# vds_topboard_revC.net
KiCad netlist of a schematic drawn in EAGLE
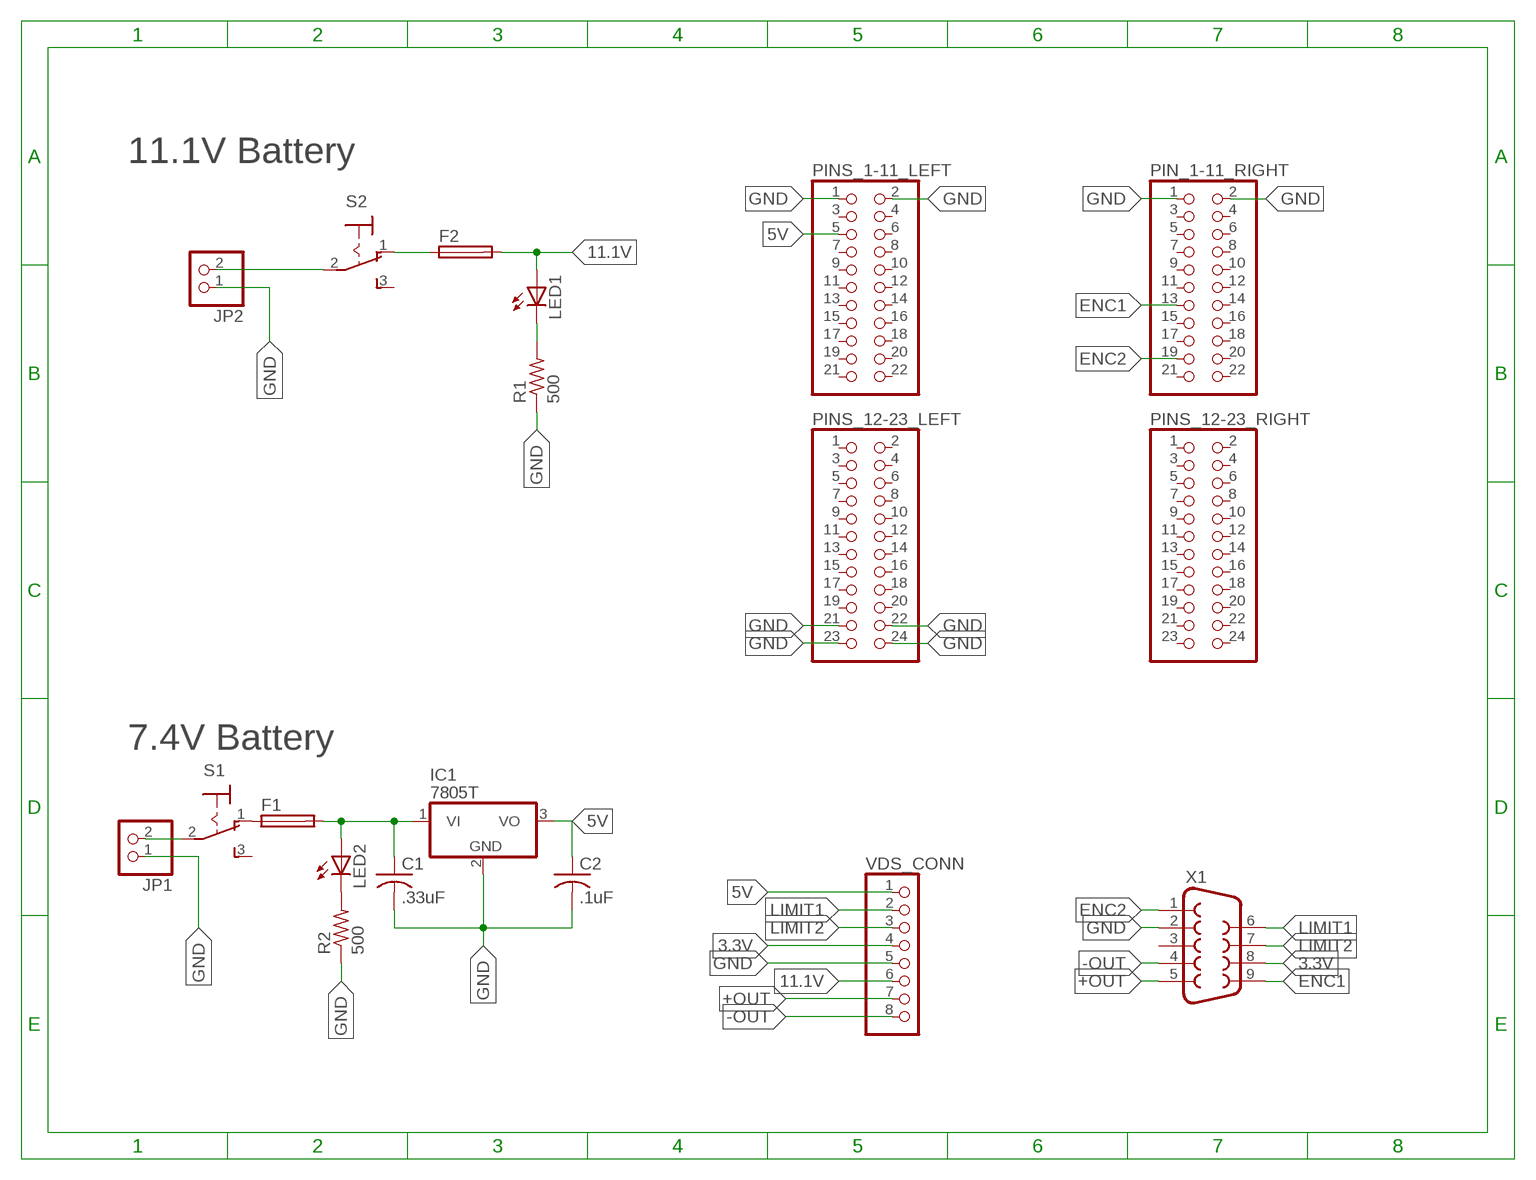
[diagram p0: schematic, sheet 1]

(export (version "E")
  (design (tool "Eeschema 10.0.6"))
  (components
    (comp (ref "C1")
      (value ".33uF")
      (footprint "eagle-import:C025-030X050")
      (libsource (lib "eagle-import") (part "C-US025-030X050"))
    )
    (comp (ref "C2")
      (value ".1uF")
      (footprint "eagle-import:C025-030X050")
      (libsource (lib "eagle-import") (part "C-US025-030X050"))
    )
    (comp (ref "F1")
      (value "SH22,5")
      (footprint "eagle-import:SH22,5")
      (fields (field (name "MF") "SCHURTER") (field (name "MPN") "0031.8201"))
      (libsource (lib "eagle-import") (part "SH22,5"))
    )
    (comp (ref "F2")
      (value "SH22,5")
      (footprint "eagle-import:SH22,5")
      (fields (field (name "MF") "SCHURTER") (field (name "MPN") "0031.8201"))
      (libsource (lib "eagle-import") (part "SH22,5"))
    )
    (comp (ref "IC1")
      (value "7805T")
      (footprint "eagle-import:TO220H")
      (libsource (lib "eagle-import") (part "78T05"))
    )
    (comp (ref "JP1")
      (value "PINHD-1X2")
      (footprint "eagle-import:1X02")
      (libsource (lib "eagle-import") (part "PINHD-1X2"))
    )
    (comp (ref "JP2")
      (value "PINHD-1X2")
      (footprint "eagle-import:1X02")
      (libsource (lib "eagle-import") (part "PINHD-1X2"))
    )
    (comp (ref "LED1")
      (value "LED5MM")
      (footprint "eagle-import:LED5MM")
      (libsource (lib "eagle-import") (part "LED5MM"))
    )
    (comp (ref "LED2")
      (value "LED5MM")
      (footprint "eagle-import:LED5MM")
      (libsource (lib "eagle-import") (part "LED5MM"))
    )
    (comp (ref "PINS_1-11_LEFT")
      (value "PINHD-2X11")
      (footprint "eagle-import:2X11")
      (libsource (lib "eagle-import") (part "PINHD-2X11"))
    )
    (comp (ref "PINS_12-23_LEFT")
      (value "PINHD-2X12")
      (footprint "eagle-import:2X12")
      (libsource (lib "eagle-import") (part "PINHD-2X12"))
    )
    (comp (ref "PINS_12-23_RIGHT")
      (value "PINHD-2X12")
      (footprint "eagle-import:2X12")
      (libsource (lib "eagle-import") (part "PINHD-2X12"))
    )
    (comp (ref "PIN_1-11_RIGHT")
      (value "PINHD-2X11")
      (footprint "eagle-import:2X11")
      (libsource (lib "eagle-import") (part "PINHD-2X11"))
    )
    (comp (ref "R1")
      (value "500")
      (footprint "eagle-import:0204_5")
      (libsource (lib "eagle-import") (part "R-US_0204/5"))
    )
    (comp (ref "R2")
      (value "500")
      (footprint "eagle-import:0204_5")
      (libsource (lib "eagle-import") (part "R-US_0204/5"))
    )
    (comp (ref "S1")
      (value "320-916")
      (footprint "eagle-import:320-916")
      (libsource (lib "eagle-import") (part "320-916"))
    )
    (comp (ref "S2")
      (value "320-916")
      (footprint "eagle-import:320-916")
      (libsource (lib "eagle-import") (part "320-916"))
    )
    (comp (ref "VDS_CONN")
      (value "PINHD-1X8")
      (footprint "eagle-import:1X08")
      (libsource (lib "eagle-import") (part "PINHD-1X8"))
    )
    (comp (ref "X1")
      (value "F09VP")
      (footprint "eagle-import:F09VP")
      (libsource (lib "eagle-import") (part "F09VP"))
    )
  )
  (nets
    (net (code "1") (name "+OUT") (class "Default")
      (node (ref "VDS_CONN") (pin "7") (pinfunction "7_7") (pintype "passive"))
      (node (ref "X1") (pin "5") (pinfunction "5_5") (pintype "passive"))
    )
    (net (code "2") (name "-OUT") (class "Default")
      (node (ref "VDS_CONN") (pin "8") (pinfunction "8_8") (pintype "passive"))
      (node (ref "X1") (pin "4") (pinfunction "4_4") (pintype "passive"))
    )
    (net (code "3") (name "3.3V") (class "Default")
      (node (ref "VDS_CONN") (pin "4") (pinfunction "4_4") (pintype "passive"))
      (node (ref "X1") (pin "8") (pinfunction "8_8") (pintype "passive"))
    )
    (net (code "4") (name "5V") (class "Default")
      (node (ref "C2") (pin "1") (pinfunction "1_1") (pintype "passive"))
      (node (ref "IC1") (pin "3") (pinfunction "VO_3") (pintype "passive"))
      (node (ref "PINS_1-11_LEFT") (pin "5") (pinfunction "5_5") (pintype "passive"))
      (node (ref "VDS_CONN") (pin "1") (pinfunction "1_1") (pintype "passive"))
    )
    (net (code "5") (name "11.1V") (class "Default")
      (node (ref "F2") (pin "2") (pinfunction "2_2") (pintype "passive"))
      (node (ref "LED1") (pin "A") (pinfunction "A_A") (pintype "passive"))
      (node (ref "VDS_CONN") (pin "6") (pinfunction "6_6") (pintype "passive"))
    )
    (net (code "6") (name "ENC1") (class "Default")
      (node (ref "PIN_1-11_RIGHT") (pin "13") (pinfunction "13_13") (pintype "passive"))
      (node (ref "X1") (pin "9") (pinfunction "9_9") (pintype "passive"))
    )
    (net (code "7") (name "ENC2") (class "Default")
      (node (ref "PIN_1-11_RIGHT") (pin "19") (pinfunction "19_19") (pintype "passive"))
      (node (ref "X1") (pin "1") (pinfunction "1_1") (pintype "passive"))
    )
    (net (code "8") (name "GND") (class "Default")
      (node (ref "C1") (pin "2") (pinfunction "2_2") (pintype "passive"))
      (node (ref "C2") (pin "2") (pinfunction "2_2") (pintype "passive"))
      (node (ref "IC1") (pin "2") (pinfunction "GND_2") (pintype "passive"))
      (node (ref "JP1") (pin "1") (pinfunction "1_1") (pintype "passive"))
      (node (ref "JP2") (pin "1") (pinfunction "1_1") (pintype "passive"))
      (node (ref "PINS_1-11_LEFT") (pin "1") (pinfunction "1_1") (pintype "passive"))
      (node (ref "PINS_1-11_LEFT") (pin "2") (pinfunction "2_2") (pintype "passive"))
      (node (ref "PINS_12-23_LEFT") (pin "21") (pinfunction "21_21") (pintype "passive"))
      (node (ref "PINS_12-23_LEFT") (pin "22") (pinfunction "22_22") (pintype "passive"))
      (node (ref "PINS_12-23_LEFT") (pin "23") (pinfunction "23_23") (pintype "passive"))
      (node (ref "PINS_12-23_LEFT") (pin "24") (pinfunction "24_24") (pintype "passive"))
      (node (ref "PIN_1-11_RIGHT") (pin "1") (pinfunction "1_1") (pintype "passive"))
      (node (ref "PIN_1-11_RIGHT") (pin "2") (pinfunction "2_2") (pintype "passive"))
      (node (ref "R1") (pin "1") (pinfunction "1_1") (pintype "passive"))
      (node (ref "R2") (pin "1") (pinfunction "1_1") (pintype "passive"))
      (node (ref "VDS_CONN") (pin "5") (pinfunction "5_5") (pintype "passive"))
      (node (ref "X1") (pin "2") (pinfunction "2_2") (pintype "passive"))
    )
    (net (code "9") (name "LIMIT1") (class "Default")
      (node (ref "VDS_CONN") (pin "2") (pinfunction "2_2") (pintype "passive"))
      (node (ref "X1") (pin "6") (pinfunction "6_6") (pintype "passive"))
    )
    (net (code "10") (name "LIMIT2") (class "Default")
      (node (ref "VDS_CONN") (pin "3") (pinfunction "3_3") (pintype "passive"))
      (node (ref "X1") (pin "7") (pinfunction "7_7") (pintype "passive"))
    )
    (net (code "11") (name "Net-(IC1-VI)") (class "Default")
      (node (ref "C1") (pin "1") (pinfunction "1_1") (pintype "passive"))
      (node (ref "F1") (pin "2") (pinfunction "2_2") (pintype "passive"))
      (node (ref "IC1") (pin "1") (pinfunction "VI_1") (pintype "input"))
      (node (ref "LED2") (pin "A") (pinfunction "A_A") (pintype "passive"))
    )
    (net (code "12") (name "Net-(LED1-C)") (class "Default")
      (node (ref "LED1") (pin "K") (pinfunction "C_K") (pintype "passive"))
      (node (ref "R1") (pin "2") (pinfunction "2_2") (pintype "passive"))
    )
    (net (code "13") (name "Net-(LED2-C)") (class "Default")
      (node (ref "LED2") (pin "K") (pinfunction "C_K") (pintype "passive"))
      (node (ref "R2") (pin "2") (pinfunction "2_2") (pintype "passive"))
    )
    (net (code "14") (name "Net-(S1-O)") (class "Default")
      (node (ref "F1") (pin "1") (pinfunction "1_1") (pintype "passive"))
      (node (ref "S1") (pin "1") (pinfunction "O_1") (pintype "passive"))
    )
    (net (code "15") (name "Net-(S1-P)") (class "Default")
      (node (ref "JP1") (pin "2") (pinfunction "2_2") (pintype "passive"))
      (node (ref "S1") (pin "2") (pinfunction "P_2") (pintype "passive"))
    )
    (net (code "16") (name "Net-(S2-O)") (class "Default")
      (node (ref "F2") (pin "1") (pinfunction "1_1") (pintype "passive"))
      (node (ref "S2") (pin "1") (pinfunction "O_1") (pintype "passive"))
    )
    (net (code "17") (name "Net-(S2-P)") (class "Default")
      (node (ref "JP2") (pin "2") (pinfunction "2_2") (pintype "passive"))
      (node (ref "S2") (pin "2") (pinfunction "P_2") (pintype "passive"))
    )
    (net (code "18") (name "unconnected-(PINS_1-11_LEFT-Pad3)") (class "Default")
      (node (ref "PINS_1-11_LEFT") (pin "3") (pinfunction "3_3") (pintype "passive"))
    )
    (net (code "19") (name "unconnected-(PINS_1-11_LEFT-Pad4)") (class "Default")
      (node (ref "PINS_1-11_LEFT") (pin "4") (pinfunction "4_4") (pintype "passive"))
    )
    (net (code "20") (name "unconnected-(PINS_1-11_LEFT-Pad6)") (class "Default")
      (node (ref "PINS_1-11_LEFT") (pin "6") (pinfunction "6_6") (pintype "passive"))
    )
    (net (code "21") (name "unconnected-(PINS_1-11_LEFT-Pad7)") (class "Default")
      (node (ref "PINS_1-11_LEFT") (pin "7") (pinfunction "7_7") (pintype "passive"))
    )
    (net (code "22") (name "unconnected-(PINS_1-11_LEFT-Pad8)") (class "Default")
      (node (ref "PINS_1-11_LEFT") (pin "8") (pinfunction "8_8") (pintype "passive"))
    )
    (net (code "23") (name "unconnected-(PINS_1-11_LEFT-Pad9)") (class "Default")
      (node (ref "PINS_1-11_LEFT") (pin "9") (pinfunction "9_9") (pintype "passive"))
    )
    (net (code "24") (name "unconnected-(PINS_1-11_LEFT-Pad10)") (class "Default")
      (node (ref "PINS_1-11_LEFT") (pin "10") (pinfunction "10_10") (pintype "passive"))
    )
    (net (code "25") (name "unconnected-(PINS_1-11_LEFT-Pad11)") (class "Default")
      (node (ref "PINS_1-11_LEFT") (pin "11") (pinfunction "11_11") (pintype "passive"))
    )
    (net (code "26") (name "unconnected-(PINS_1-11_LEFT-Pad12)") (class "Default")
      (node (ref "PINS_1-11_LEFT") (pin "12") (pinfunction "12_12") (pintype "passive"))
    )
    (net (code "27") (name "unconnected-(PINS_1-11_LEFT-Pad13)") (class "Default")
      (node (ref "PINS_1-11_LEFT") (pin "13") (pinfunction "13_13") (pintype "passive"))
    )
    (net (code "28") (name "unconnected-(PINS_1-11_LEFT-Pad14)") (class "Default")
      (node (ref "PINS_1-11_LEFT") (pin "14") (pinfunction "14_14") (pintype "passive"))
    )
    (net (code "29") (name "unconnected-(PINS_1-11_LEFT-Pad15)") (class "Default")
      (node (ref "PINS_1-11_LEFT") (pin "15") (pinfunction "15_15") (pintype "passive"))
    )
    (net (code "30") (name "unconnected-(PINS_1-11_LEFT-Pad16)") (class "Default")
      (node (ref "PINS_1-11_LEFT") (pin "16") (pinfunction "16_16") (pintype "passive"))
    )
    (net (code "31") (name "unconnected-(PINS_1-11_LEFT-Pad17)") (class "Default")
      (node (ref "PINS_1-11_LEFT") (pin "17") (pinfunction "17_17") (pintype "passive"))
    )
    (net (code "32") (name "unconnected-(PINS_1-11_LEFT-Pad18)") (class "Default")
      (node (ref "PINS_1-11_LEFT") (pin "18") (pinfunction "18_18") (pintype "passive"))
    )
    (net (code "33") (name "unconnected-(PINS_1-11_LEFT-Pad19)") (class "Default")
      (node (ref "PINS_1-11_LEFT") (pin "19") (pinfunction "19_19") (pintype "passive"))
    )
    (net (code "34") (name "unconnected-(PINS_1-11_LEFT-Pad20)") (class "Default")
      (node (ref "PINS_1-11_LEFT") (pin "20") (pinfunction "20_20") (pintype "passive"))
    )
    (net (code "35") (name "unconnected-(PINS_1-11_LEFT-Pad21)") (class "Default")
      (node (ref "PINS_1-11_LEFT") (pin "21") (pinfunction "21_21") (pintype "passive"))
    )
    (net (code "36") (name "unconnected-(PINS_1-11_LEFT-Pad22)") (class "Default")
      (node (ref "PINS_1-11_LEFT") (pin "22") (pinfunction "22_22") (pintype "passive"))
    )
    (net (code "37") (name "unconnected-(PINS_12-23_LEFT-Pad1)") (class "Default")
      (node (ref "PINS_12-23_LEFT") (pin "1") (pinfunction "1_1") (pintype "passive"))
    )
    (net (code "38") (name "unconnected-(PINS_12-23_LEFT-Pad2)") (class "Default")
      (node (ref "PINS_12-23_LEFT") (pin "2") (pinfunction "2_2") (pintype "passive"))
    )
    (net (code "39") (name "unconnected-(PINS_12-23_LEFT-Pad3)") (class "Default")
      (node (ref "PINS_12-23_LEFT") (pin "3") (pinfunction "3_3") (pintype "passive"))
    )
    (net (code "40") (name "unconnected-(PINS_12-23_LEFT-Pad4)") (class "Default")
      (node (ref "PINS_12-23_LEFT") (pin "4") (pinfunction "4_4") (pintype "passive"))
    )
    (net (code "41") (name "unconnected-(PINS_12-23_LEFT-Pad5)") (class "Default")
      (node (ref "PINS_12-23_LEFT") (pin "5") (pinfunction "5_5") (pintype "passive"))
    )
    (net (code "42") (name "unconnected-(PINS_12-23_LEFT-Pad6)") (class "Default")
      (node (ref "PINS_12-23_LEFT") (pin "6") (pinfunction "6_6") (pintype "passive"))
    )
    (net (code "43") (name "unconnected-(PINS_12-23_LEFT-Pad7)") (class "Default")
      (node (ref "PINS_12-23_LEFT") (pin "7") (pinfunction "7_7") (pintype "passive"))
    )
    (net (code "44") (name "unconnected-(PINS_12-23_LEFT-Pad8)") (class "Default")
      (node (ref "PINS_12-23_LEFT") (pin "8") (pinfunction "8_8") (pintype "passive"))
    )
    (net (code "45") (name "unconnected-(PINS_12-23_LEFT-Pad9)") (class "Default")
      (node (ref "PINS_12-23_LEFT") (pin "9") (pinfunction "9_9") (pintype "passive"))
    )
    (net (code "46") (name "unconnected-(PINS_12-23_LEFT-Pad10)") (class "Default")
      (node (ref "PINS_12-23_LEFT") (pin "10") (pinfunction "10_10") (pintype "passive"))
    )
    (net (code "47") (name "unconnected-(PINS_12-23_LEFT-Pad11)") (class "Default")
      (node (ref "PINS_12-23_LEFT") (pin "11") (pinfunction "11_11") (pintype "passive"))
    )
    (net (code "48") (name "unconnected-(PINS_12-23_LEFT-Pad12)") (class "Default")
      (node (ref "PINS_12-23_LEFT") (pin "12") (pinfunction "12_12") (pintype "passive"))
    )
    (net (code "49") (name "unconnected-(PINS_12-23_LEFT-Pad13)") (class "Default")
      (node (ref "PINS_12-23_LEFT") (pin "13") (pinfunction "13_13") (pintype "passive"))
    )
    (net (code "50") (name "unconnected-(PINS_12-23_LEFT-Pad14)") (class "Default")
      (node (ref "PINS_12-23_LEFT") (pin "14") (pinfunction "14_14") (pintype "passive"))
    )
    (net (code "51") (name "unconnected-(PINS_12-23_LEFT-Pad15)") (class "Default")
      (node (ref "PINS_12-23_LEFT") (pin "15") (pinfunction "15_15") (pintype "passive"))
    )
    (net (code "52") (name "unconnected-(PINS_12-23_LEFT-Pad16)") (class "Default")
      (node (ref "PINS_12-23_LEFT") (pin "16") (pinfunction "16_16") (pintype "passive"))
    )
    (net (code "53") (name "unconnected-(PINS_12-23_LEFT-Pad17)") (class "Default")
      (node (ref "PINS_12-23_LEFT") (pin "17") (pinfunction "17_17") (pintype "passive"))
    )
    (net (code "54") (name "unconnected-(PINS_12-23_LEFT-Pad18)") (class "Default")
      (node (ref "PINS_12-23_LEFT") (pin "18") (pinfunction "18_18") (pintype "passive"))
    )
    (net (code "55") (name "unconnected-(PINS_12-23_LEFT-Pad19)") (class "Default")
      (node (ref "PINS_12-23_LEFT") (pin "19") (pinfunction "19_19") (pintype "passive"))
    )
    (net (code "56") (name "unconnected-(PINS_12-23_LEFT-Pad20)") (class "Default")
      (node (ref "PINS_12-23_LEFT") (pin "20") (pinfunction "20_20") (pintype "passive"))
    )
    (net (code "57") (name "unconnected-(PINS_12-23_RIGHT-Pad1)") (class "Default")
      (node (ref "PINS_12-23_RIGHT") (pin "1") (pinfunction "1_1") (pintype "passive"))
    )
    (net (code "58") (name "unconnected-(PINS_12-23_RIGHT-Pad2)") (class "Default")
      (node (ref "PINS_12-23_RIGHT") (pin "2") (pinfunction "2_2") (pintype "passive"))
    )
    (net (code "59") (name "unconnected-(PINS_12-23_RIGHT-Pad3)") (class "Default")
      (node (ref "PINS_12-23_RIGHT") (pin "3") (pinfunction "3_3") (pintype "passive"))
    )
    (net (code "60") (name "unconnected-(PINS_12-23_RIGHT-Pad4)") (class "Default")
      (node (ref "PINS_12-23_RIGHT") (pin "4") (pinfunction "4_4") (pintype "passive"))
    )
    (net (code "61") (name "unconnected-(PINS_12-23_RIGHT-Pad5)") (class "Default")
      (node (ref "PINS_12-23_RIGHT") (pin "5") (pinfunction "5_5") (pintype "passive"))
    )
    (net (code "62") (name "unconnected-(PINS_12-23_RIGHT-Pad6)") (class "Default")
      (node (ref "PINS_12-23_RIGHT") (pin "6") (pinfunction "6_6") (pintype "passive"))
    )
    (net (code "63") (name "unconnected-(PINS_12-23_RIGHT-Pad7)") (class "Default")
      (node (ref "PINS_12-23_RIGHT") (pin "7") (pinfunction "7_7") (pintype "passive"))
    )
    (net (code "64") (name "unconnected-(PINS_12-23_RIGHT-Pad8)") (class "Default")
      (node (ref "PINS_12-23_RIGHT") (pin "8") (pinfunction "8_8") (pintype "passive"))
    )
    (net (code "65") (name "unconnected-(PINS_12-23_RIGHT-Pad9)") (class "Default")
      (node (ref "PINS_12-23_RIGHT") (pin "9") (pinfunction "9_9") (pintype "passive"))
    )
    (net (code "66") (name "unconnected-(PINS_12-23_RIGHT-Pad10)") (class "Default")
      (node (ref "PINS_12-23_RIGHT") (pin "10") (pinfunction "10_10") (pintype "passive"))
    )
    (net (code "67") (name "unconnected-(PINS_12-23_RIGHT-Pad11)") (class "Default")
      (node (ref "PINS_12-23_RIGHT") (pin "11") (pinfunction "11_11") (pintype "passive"))
    )
    (net (code "68") (name "unconnected-(PINS_12-23_RIGHT-Pad12)") (class "Default")
      (node (ref "PINS_12-23_RIGHT") (pin "12") (pinfunction "12_12") (pintype "passive"))
    )
    (net (code "69") (name "unconnected-(PINS_12-23_RIGHT-Pad13)") (class "Default")
      (node (ref "PINS_12-23_RIGHT") (pin "13") (pinfunction "13_13") (pintype "passive"))
    )
    (net (code "70") (name "unconnected-(PINS_12-23_RIGHT-Pad14)") (class "Default")
      (node (ref "PINS_12-23_RIGHT") (pin "14") (pinfunction "14_14") (pintype "passive"))
    )
    (net (code "71") (name "unconnected-(PINS_12-23_RIGHT-Pad15)") (class "Default")
      (node (ref "PINS_12-23_RIGHT") (pin "15") (pinfunction "15_15") (pintype "passive"))
    )
    (net (code "72") (name "unconnected-(PINS_12-23_RIGHT-Pad16)") (class "Default")
      (node (ref "PINS_12-23_RIGHT") (pin "16") (pinfunction "16_16") (pintype "passive"))
    )
    (net (code "73") (name "unconnected-(PINS_12-23_RIGHT-Pad17)") (class "Default")
      (node (ref "PINS_12-23_RIGHT") (pin "17") (pinfunction "17_17") (pintype "passive"))
    )
    (net (code "74") (name "unconnected-(PINS_12-23_RIGHT-Pad18)") (class "Default")
      (node (ref "PINS_12-23_RIGHT") (pin "18") (pinfunction "18_18") (pintype "passive"))
    )
    (net (code "75") (name "unconnected-(PINS_12-23_RIGHT-Pad19)") (class "Default")
      (node (ref "PINS_12-23_RIGHT") (pin "19") (pinfunction "19_19") (pintype "passive"))
    )
    (net (code "76") (name "unconnected-(PINS_12-23_RIGHT-Pad20)") (class "Default")
      (node (ref "PINS_12-23_RIGHT") (pin "20") (pinfunction "20_20") (pintype "passive"))
    )
    (net (code "77") (name "unconnected-(PINS_12-23_RIGHT-Pad21)") (class "Default")
      (node (ref "PINS_12-23_RIGHT") (pin "21") (pinfunction "21_21") (pintype "passive"))
    )
    (net (code "78") (name "unconnected-(PINS_12-23_RIGHT-Pad22)") (class "Default")
      (node (ref "PINS_12-23_RIGHT") (pin "22") (pinfunction "22_22") (pintype "passive"))
    )
    (net (code "79") (name "unconnected-(PINS_12-23_RIGHT-Pad23)") (class "Default")
      (node (ref "PINS_12-23_RIGHT") (pin "23") (pinfunction "23_23") (pintype "passive"))
    )
    (net (code "80") (name "unconnected-(PINS_12-23_RIGHT-Pad24)") (class "Default")
      (node (ref "PINS_12-23_RIGHT") (pin "24") (pinfunction "24_24") (pintype "passive"))
    )
    (net (code "81") (name "unconnected-(PIN_1-11_RIGHT-Pad3)") (class "Default")
      (node (ref "PIN_1-11_RIGHT") (pin "3") (pinfunction "3_3") (pintype "passive"))
    )
    (net (code "82") (name "unconnected-(PIN_1-11_RIGHT-Pad4)") (class "Default")
      (node (ref "PIN_1-11_RIGHT") (pin "4") (pinfunction "4_4") (pintype "passive"))
    )
    (net (code "83") (name "unconnected-(PIN_1-11_RIGHT-Pad5)") (class "Default")
      (node (ref "PIN_1-11_RIGHT") (pin "5") (pinfunction "5_5") (pintype "passive"))
    )
    (net (code "84") (name "unconnected-(PIN_1-11_RIGHT-Pad6)") (class "Default")
      (node (ref "PIN_1-11_RIGHT") (pin "6") (pinfunction "6_6") (pintype "passive"))
    )
    (net (code "85") (name "unconnected-(PIN_1-11_RIGHT-Pad7)") (class "Default")
      (node (ref "PIN_1-11_RIGHT") (pin "7") (pinfunction "7_7") (pintype "passive"))
    )
    (net (code "86") (name "unconnected-(PIN_1-11_RIGHT-Pad8)") (class "Default")
      (node (ref "PIN_1-11_RIGHT") (pin "8") (pinfunction "8_8") (pintype "passive"))
    )
    (net (code "87") (name "unconnected-(PIN_1-11_RIGHT-Pad9)") (class "Default")
      (node (ref "PIN_1-11_RIGHT") (pin "9") (pinfunction "9_9") (pintype "passive"))
    )
    (net (code "88") (name "unconnected-(PIN_1-11_RIGHT-Pad10)") (class "Default")
      (node (ref "PIN_1-11_RIGHT") (pin "10") (pinfunction "10_10") (pintype "passive"))
    )
    (net (code "89") (name "unconnected-(PIN_1-11_RIGHT-Pad11)") (class "Default")
      (node (ref "PIN_1-11_RIGHT") (pin "11") (pinfunction "11_11") (pintype "passive"))
    )
    (net (code "90") (name "unconnected-(PIN_1-11_RIGHT-Pad12)") (class "Default")
      (node (ref "PIN_1-11_RIGHT") (pin "12") (pinfunction "12_12") (pintype "passive"))
    )
    (net (code "91") (name "unconnected-(PIN_1-11_RIGHT-Pad14)") (class "Default")
      (node (ref "PIN_1-11_RIGHT") (pin "14") (pinfunction "14_14") (pintype "passive"))
    )
    (net (code "92") (name "unconnected-(PIN_1-11_RIGHT-Pad15)") (class "Default")
      (node (ref "PIN_1-11_RIGHT") (pin "15") (pinfunction "15_15") (pintype "passive"))
    )
    (net (code "93") (name "unconnected-(PIN_1-11_RIGHT-Pad16)") (class "Default")
      (node (ref "PIN_1-11_RIGHT") (pin "16") (pinfunction "16_16") (pintype "passive"))
    )
    (net (code "94") (name "unconnected-(PIN_1-11_RIGHT-Pad17)") (class "Default")
      (node (ref "PIN_1-11_RIGHT") (pin "17") (pinfunction "17_17") (pintype "passive"))
    )
    (net (code "95") (name "unconnected-(PIN_1-11_RIGHT-Pad18)") (class "Default")
      (node (ref "PIN_1-11_RIGHT") (pin "18") (pinfunction "18_18") (pintype "passive"))
    )
    (net (code "96") (name "unconnected-(PIN_1-11_RIGHT-Pad20)") (class "Default")
      (node (ref "PIN_1-11_RIGHT") (pin "20") (pinfunction "20_20") (pintype "passive"))
    )
    (net (code "97") (name "unconnected-(PIN_1-11_RIGHT-Pad21)") (class "Default")
      (node (ref "PIN_1-11_RIGHT") (pin "21") (pinfunction "21_21") (pintype "passive"))
    )
    (net (code "98") (name "unconnected-(PIN_1-11_RIGHT-Pad22)") (class "Default")
      (node (ref "PIN_1-11_RIGHT") (pin "22") (pinfunction "22_22") (pintype "passive"))
    )
    (net (code "99") (name "unconnected-(S1-S-Pad3)") (class "Default")
      (node (ref "S1") (pin "3") (pinfunction "S_3") (pintype "passive"))
    )
    (net (code "100") (name "unconnected-(S2-S-Pad3)") (class "Default")
      (node (ref "S2") (pin "3") (pinfunction "S_3") (pintype "passive"))
    )
    (net (code "101") (name "unconnected-(X1-Pad3)") (class "Default")
      (node (ref "X1") (pin "3") (pinfunction "3_3") (pintype "passive"))
    )
  )
)
